# 7segement4minidigits1badidea-max7219-smd.net
KiCad netlist of a schematic drawn in EAGLE
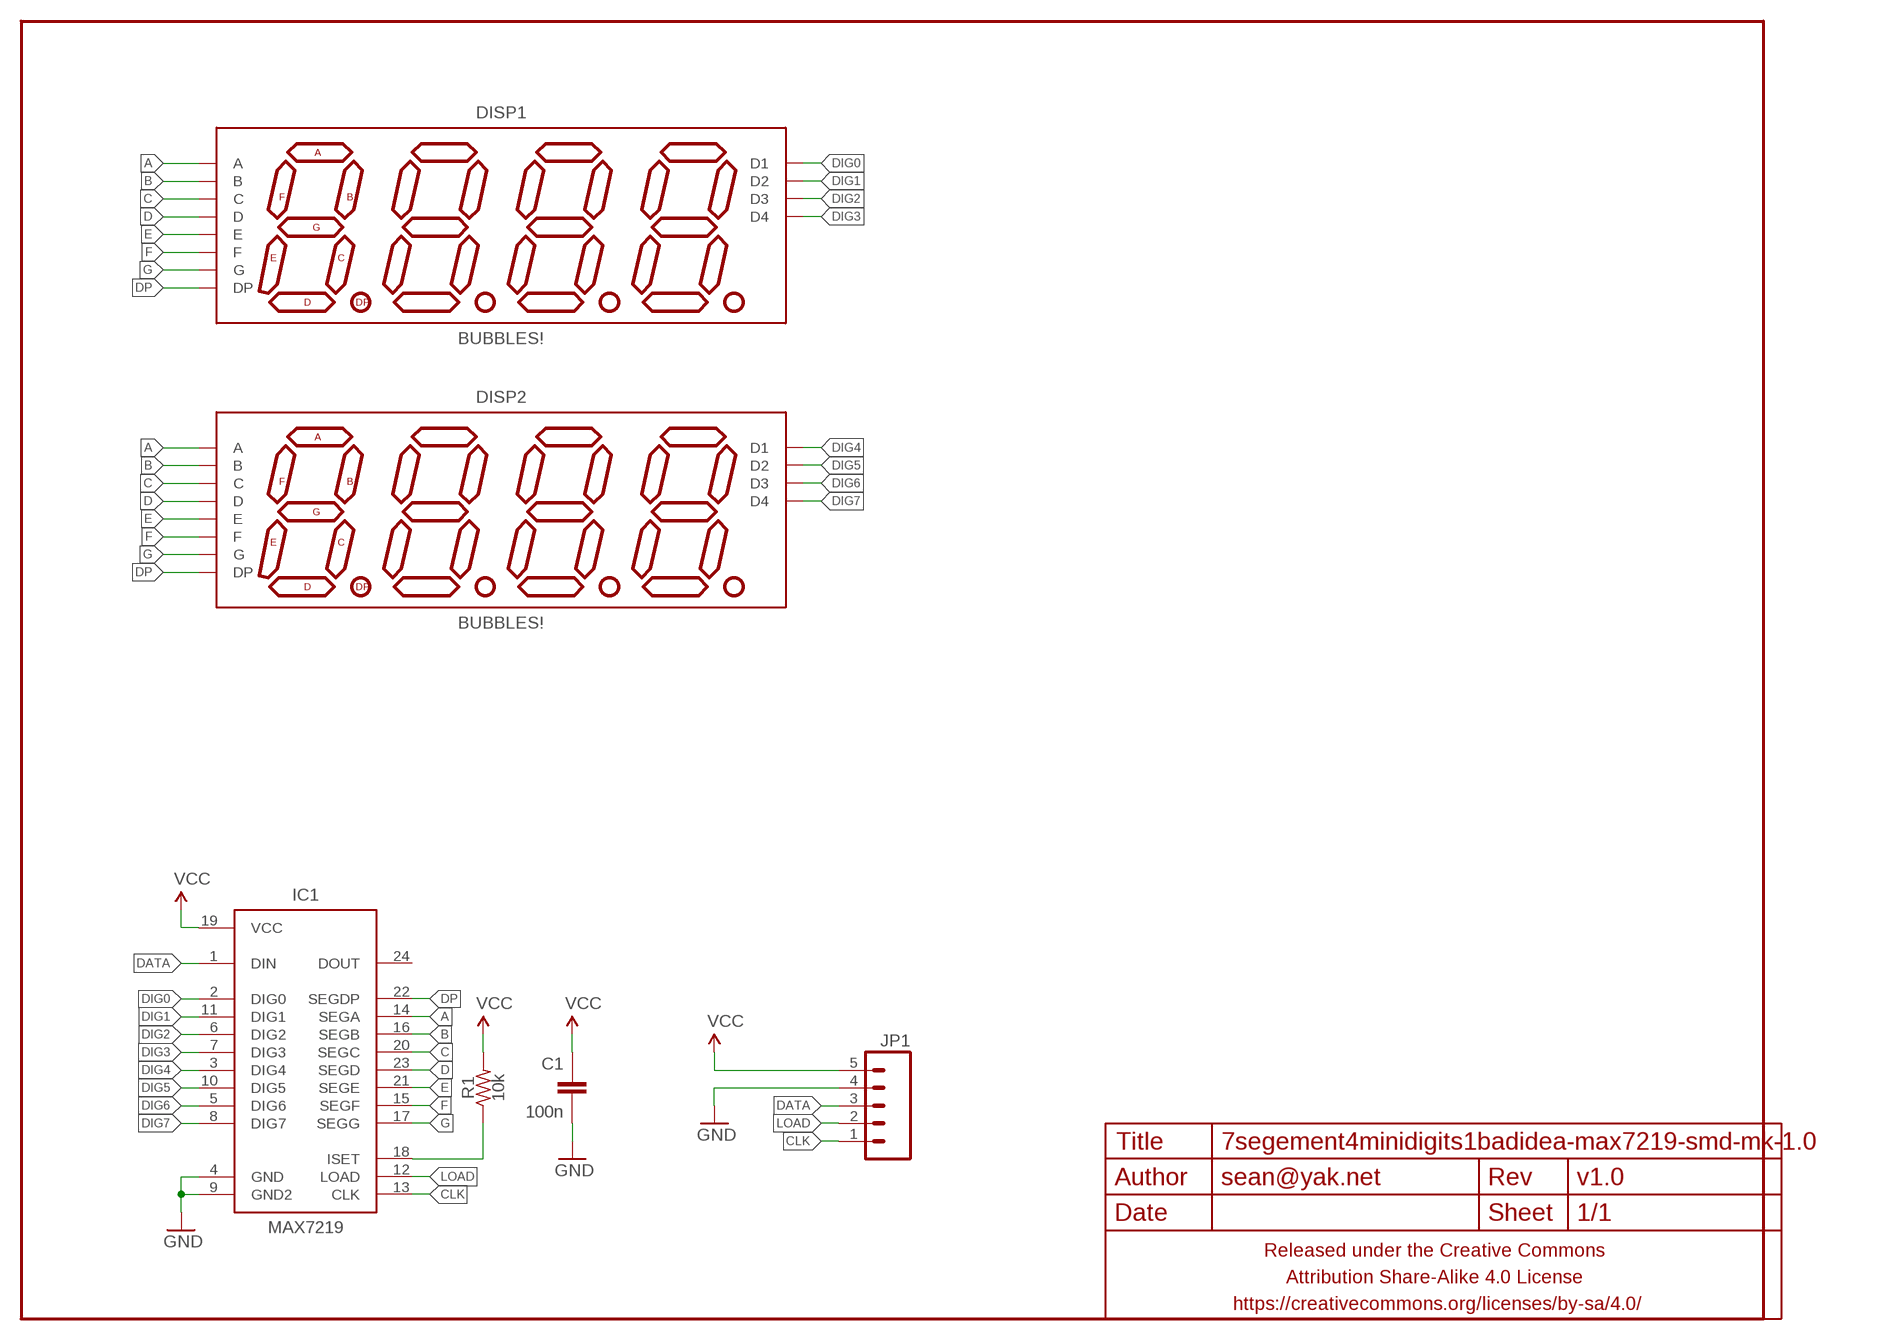
[diagram p0: schematic, sheet 1]

(export (version "E")
  (design (tool "Eeschema 10.0.6"))
  (components
    (comp (ref "C1")
      (value "100n")
      (footprint "eagle-import:C0603")
      (libsource (lib "eagle-import") (part "CAPACITOR-CERAMICC0603"))
    )
    (comp (ref "DISP1")
      (value "BUBBLES!")
      (footprint "eagle-import:DIL12")
      (libsource (lib "eagle-import") (part "7SEG_4DIGITHP-BUBBLE"))
    )
    (comp (ref "DISP2")
      (value "BUBBLES!")
      (footprint "eagle-import:DIL12")
      (libsource (lib "eagle-import") (part "7SEG_4DIGITHP-BUBBLE"))
    )
    (comp (ref "FRAME1")
      (value "FRAME-LETTERNO_PACKAGE")
      (footprint "eagle-import:DUMMY")
      (fields (field (name "DESIGNER") "sean@yak.net") (field (name "VERSION") "v1.0"))
      (libsource (lib "eagle-import") (part "FRAME-LETTERNO_PACKAGE"))
    )
    (comp (ref "IC1")
      (value "MAX7219")
      (footprint "eagle-import:SO24W")
      (libsource (lib "eagle-import") (part "MAX7219SOIC-W"))
    )
    (comp (ref "JP1")
      (value "M05PTH-CENTERED")
      (footprint "eagle-import:1X05_PTH_CENTERED")
      (libsource (lib "eagle-import") (part "M05PTH-CENTERED"))
    )
    (comp (ref "R1")
      (value "10k")
      (footprint "eagle-import:R0603")
      (libsource (lib "eagle-import") (part "RESISTORR0603"))
    )
  )
  (nets
    (net (code "1") (name "A") (class "Default")
      (node (ref "DISP1") (pin "12") (pinfunction "A_12") (pintype "bidirectional"))
      (node (ref "DISP2") (pin "12") (pinfunction "A_12") (pintype "bidirectional"))
      (node (ref "IC1") (pin "14") (pinfunction "SEGA_14") (pintype "bidirectional"))
    )
    (net (code "2") (name "B") (class "Default")
      (node (ref "DISP1") (pin "11") (pinfunction "B_11") (pintype "bidirectional"))
      (node (ref "DISP2") (pin "11") (pinfunction "B_11") (pintype "bidirectional"))
      (node (ref "IC1") (pin "16") (pinfunction "SEGB_16") (pintype "bidirectional"))
    )
    (net (code "3") (name "C") (class "Default")
      (node (ref "DISP1") (pin "3") (pinfunction "C_3") (pintype "bidirectional"))
      (node (ref "DISP2") (pin "3") (pinfunction "C_3") (pintype "bidirectional"))
      (node (ref "IC1") (pin "20") (pinfunction "SEGC_20") (pintype "bidirectional"))
    )
    (net (code "4") (name "CLK") (class "Default")
      (node (ref "IC1") (pin "13") (pinfunction "CLK_13") (pintype "bidirectional"))
      (node (ref "JP1") (pin "1") (pinfunction "1_1") (pintype "passive"))
    )
    (net (code "5") (name "D") (class "Default")
      (node (ref "DISP1") (pin "8") (pinfunction "D_8") (pintype "bidirectional"))
      (node (ref "DISP2") (pin "8") (pinfunction "D_8") (pintype "bidirectional"))
      (node (ref "IC1") (pin "23") (pinfunction "SEGD_23") (pintype "bidirectional"))
    )
    (net (code "6") (name "DATA") (class "Default")
      (node (ref "IC1") (pin "1") (pinfunction "DIN_1") (pintype "bidirectional"))
      (node (ref "JP1") (pin "3") (pinfunction "3_3") (pintype "passive"))
    )
    (net (code "7") (name "DIG0") (class "Default")
      (node (ref "DISP1") (pin "1") (pinfunction "D1_1") (pintype "bidirectional"))
      (node (ref "IC1") (pin "2") (pinfunction "DIG0_2") (pintype "bidirectional"))
    )
    (net (code "8") (name "DIG1") (class "Default")
      (node (ref "DISP1") (pin "10") (pinfunction "D2_10") (pintype "bidirectional"))
      (node (ref "IC1") (pin "11") (pinfunction "DIG1_11") (pintype "bidirectional"))
    )
    (net (code "9") (name "DIG2") (class "Default")
      (node (ref "DISP1") (pin "4") (pinfunction "D3_4") (pintype "bidirectional"))
      (node (ref "IC1") (pin "6") (pinfunction "DIG2_6") (pintype "bidirectional"))
    )
    (net (code "10") (name "DIG3") (class "Default")
      (node (ref "DISP1") (pin "6") (pinfunction "D4_6") (pintype "bidirectional"))
      (node (ref "IC1") (pin "7") (pinfunction "DIG3_7") (pintype "bidirectional"))
    )
    (net (code "11") (name "DIG4") (class "Default")
      (node (ref "DISP2") (pin "1") (pinfunction "D1_1") (pintype "bidirectional"))
      (node (ref "IC1") (pin "3") (pinfunction "DIG4_3") (pintype "bidirectional"))
    )
    (net (code "12") (name "DIG5") (class "Default")
      (node (ref "DISP2") (pin "10") (pinfunction "D2_10") (pintype "bidirectional"))
      (node (ref "IC1") (pin "10") (pinfunction "DIG5_10") (pintype "bidirectional"))
    )
    (net (code "13") (name "DIG6") (class "Default")
      (node (ref "DISP2") (pin "4") (pinfunction "D3_4") (pintype "bidirectional"))
      (node (ref "IC1") (pin "5") (pinfunction "DIG6_5") (pintype "bidirectional"))
    )
    (net (code "14") (name "DIG7") (class "Default")
      (node (ref "DISP2") (pin "6") (pinfunction "D4_6") (pintype "bidirectional"))
      (node (ref "IC1") (pin "8") (pinfunction "DIG7_8") (pintype "bidirectional"))
    )
    (net (code "15") (name "DP") (class "Default")
      (node (ref "DISP1") (pin "5") (pinfunction "DP_5") (pintype "bidirectional"))
      (node (ref "DISP2") (pin "5") (pinfunction "DP_5") (pintype "bidirectional"))
      (node (ref "IC1") (pin "22") (pinfunction "SEGDP_22") (pintype "bidirectional"))
    )
    (net (code "16") (name "E") (class "Default")
      (node (ref "DISP1") (pin "2") (pinfunction "E_2") (pintype "bidirectional"))
      (node (ref "DISP2") (pin "2") (pinfunction "E_2") (pintype "bidirectional"))
      (node (ref "IC1") (pin "21") (pinfunction "SEGE_21") (pintype "bidirectional"))
    )
    (net (code "17") (name "F") (class "Default")
      (node (ref "DISP1") (pin "9") (pinfunction "F_9") (pintype "bidirectional"))
      (node (ref "DISP2") (pin "9") (pinfunction "F_9") (pintype "bidirectional"))
      (node (ref "IC1") (pin "15") (pinfunction "SEGF_15") (pintype "bidirectional"))
    )
    (net (code "18") (name "G") (class "Default")
      (node (ref "DISP1") (pin "7") (pinfunction "G_7") (pintype "bidirectional"))
      (node (ref "DISP2") (pin "7") (pinfunction "G_7") (pintype "bidirectional"))
      (node (ref "IC1") (pin "17") (pinfunction "SEGG_17") (pintype "bidirectional"))
    )
    (net (code "19") (name "GND") (class "Default")
      (node (ref "C1") (pin "2") (pinfunction "2_2") (pintype "passive"))
      (node (ref "IC1") (pin "4") (pinfunction "GND_4") (pintype "bidirectional"))
      (node (ref "IC1") (pin "9") (pinfunction "GND2_9") (pintype "bidirectional"))
      (node (ref "JP1") (pin "4") (pinfunction "4_4") (pintype "passive"))
    )
    (net (code "20") (name "LOAD") (class "Default")
      (node (ref "IC1") (pin "12") (pinfunction "LOAD_12") (pintype "bidirectional"))
      (node (ref "JP1") (pin "2") (pinfunction "2_2") (pintype "passive"))
    )
    (net (code "21") (name "Net-(IC1-ISET)") (class "Default")
      (node (ref "IC1") (pin "18") (pinfunction "ISET_18") (pintype "bidirectional"))
      (node (ref "R1") (pin "1") (pinfunction "1_1") (pintype "passive"))
    )
    (net (code "22") (name "VCC") (class "Default")
      (node (ref "C1") (pin "1") (pinfunction "1_1") (pintype "passive"))
      (node (ref "IC1") (pin "19") (pinfunction "VCC_19") (pintype "bidirectional"))
      (node (ref "JP1") (pin "5") (pinfunction "5_5") (pintype "passive"))
      (node (ref "R1") (pin "2") (pinfunction "2_2") (pintype "passive"))
    )
    (net (code "23") (name "unconnected-(IC1-DOUT-Pad24)") (class "Default")
      (node (ref "IC1") (pin "24") (pinfunction "DOUT_24") (pintype "bidirectional"))
    )
  )
)
